# LoRaPi-0.net
KiCad netlist of a schematic drawn in EAGLE
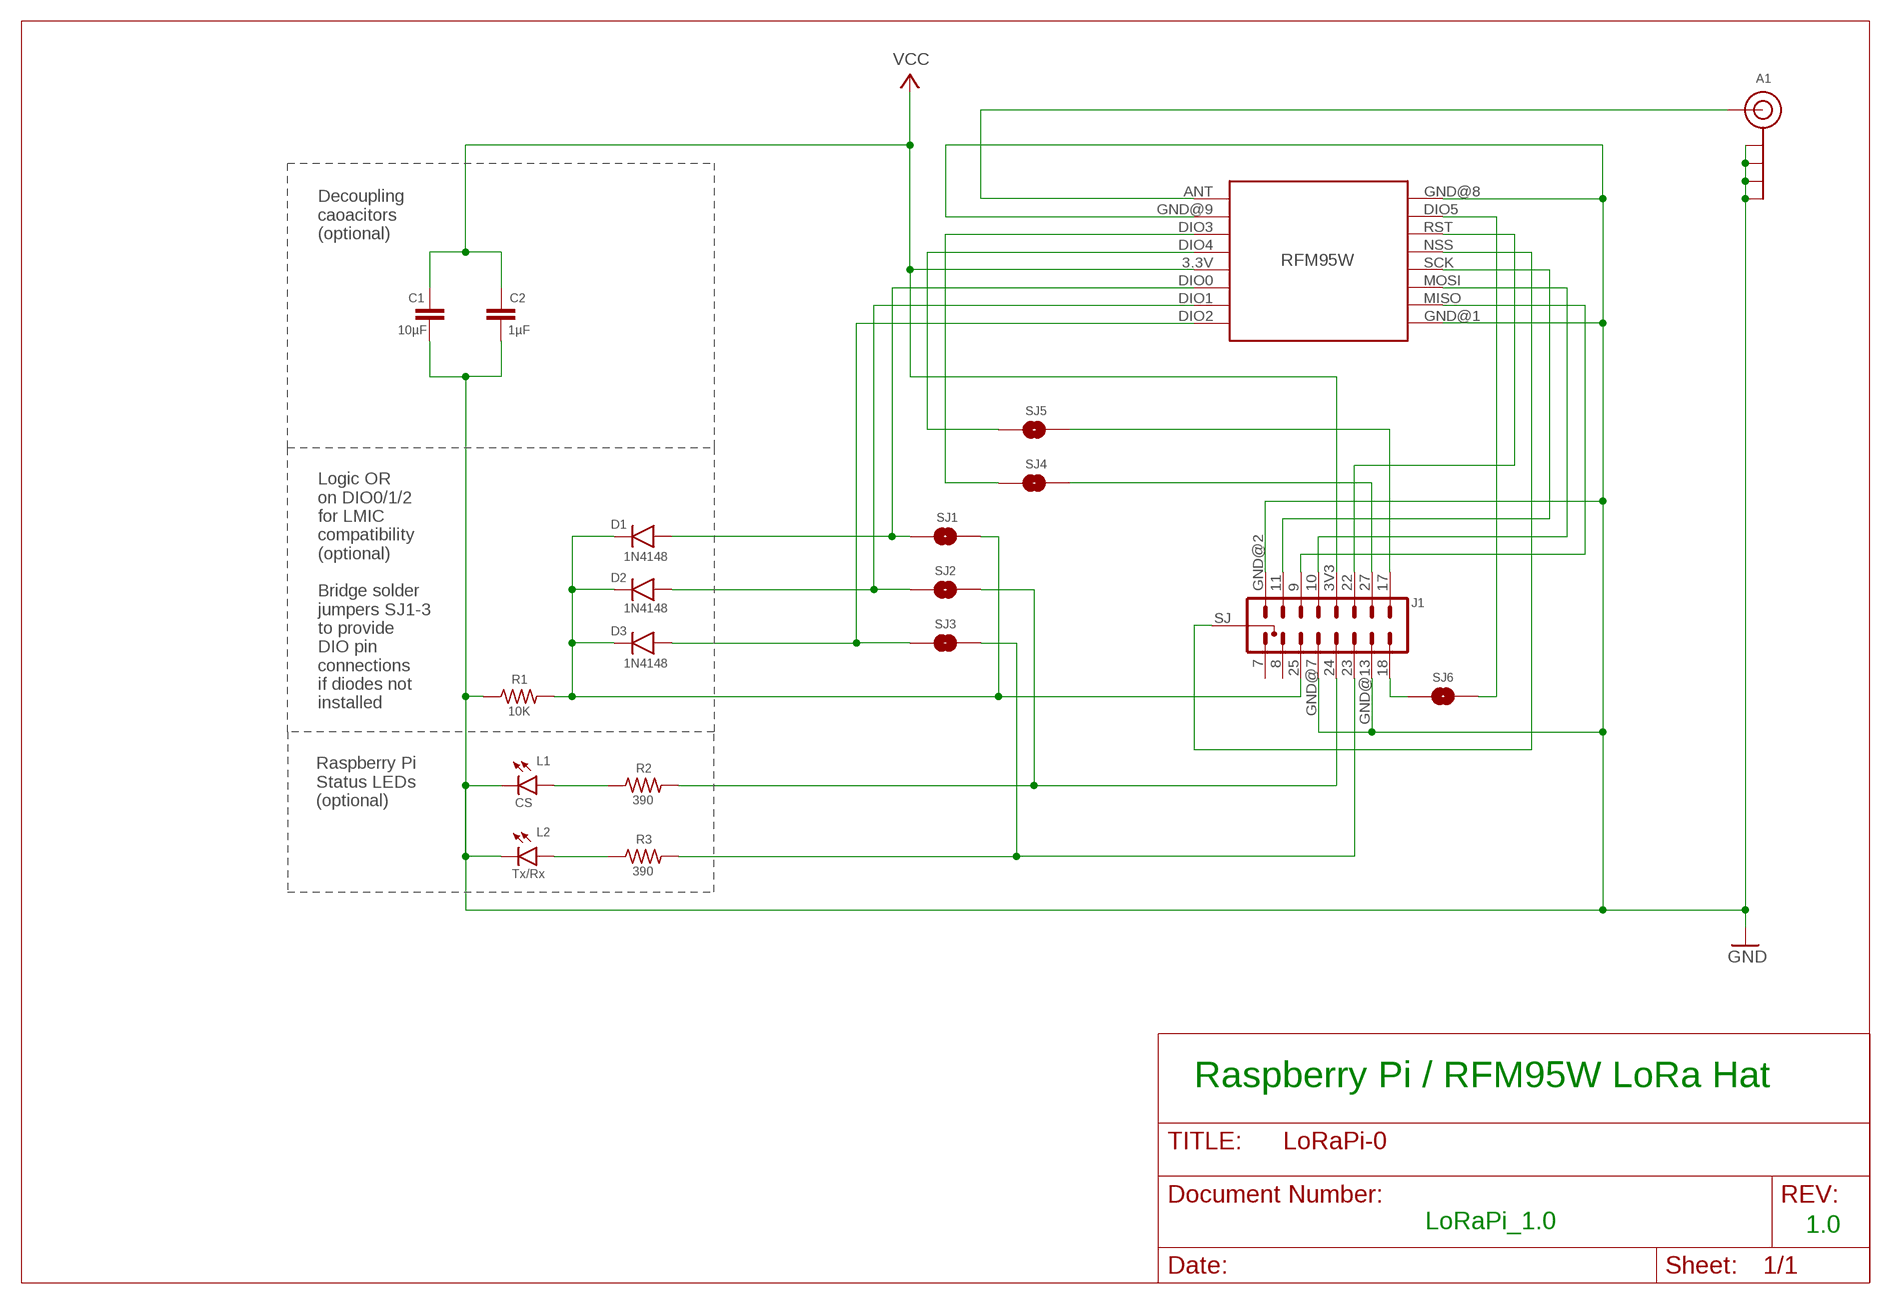
[diagram p0: schematic, sheet 1]

(export (version "E")
  (design (tool "Eeschema 10.0.6"))
  (components
    (comp (ref "A1")
      (value "U.FL-SMA-EDGE-COMBO")
      (footprint "eagle-import:U.FL-SMA-EDGE-COMBO")
      (libsource (lib "eagle-import") (part "U.FL-SMA-EDGE-COMBO"))
    )
    (comp (ref "C1")
      (value "10µF")
      (footprint "eagle-import:C0805")
      (libsource (lib "eagle-import") (part "CAPACITOR"))
    )
    (comp (ref "C2")
      (value "1µF")
      (footprint "eagle-import:C0805")
      (libsource (lib "eagle-import") (part "CAPACITOR"))
    )
    (comp (ref "D1")
      (value "1N4148")
      (footprint "eagle-import:SOD-123")
      (libsource (lib "eagle-import") (part "1N4148SMD"))
    )
    (comp (ref "D2")
      (value "1N4148")
      (footprint "eagle-import:SOD-123")
      (libsource (lib "eagle-import") (part "1N4148SMD"))
    )
    (comp (ref "D3")
      (value "1N4148")
      (footprint "eagle-import:SOD-123")
      (libsource (lib "eagle-import") (part "1N4148SMD"))
    )
    (comp (ref "J1")
      (value "HEADER-2X8-RFM95W-PI")
      (footprint "eagle-import:CONN_2X8-RFM-PI")
      (libsource (lib "eagle-import") (part "HEADER-2X8-RFM95W-PI"))
    )
    (comp (ref "L1")
      (value "CS")
      (footprint "eagle-import:CHIP-LED0805")
      (libsource (lib "eagle-import") (part "LEDCHIP-LED0805"))
    )
    (comp (ref "L2")
      (value "Tx/Rx")
      (footprint "eagle-import:CHIP-LED0805")
      (libsource (lib "eagle-import") (part "LEDCHIP-LED0805"))
    )
    (comp (ref "R1")
      (value "10K")
      (footprint "eagle-import:R0805")
      (libsource (lib "eagle-import") (part "R-US_R0805"))
    )
    (comp (ref "R2")
      (value "390")
      (footprint "eagle-import:R0805")
      (libsource (lib "eagle-import") (part "R-US_R0805"))
    )
    (comp (ref "R3")
      (value "390")
      (footprint "eagle-import:R0805")
      (libsource (lib "eagle-import") (part "R-US_R0805"))
    )
    (comp (ref "RFM95W")
      (value "RFM95W-LORA")
      (footprint "eagle-import:RFM95W-LORA")
      (libsource (lib "eagle-import") (part "RFM95W-LORA"))
    )
    (comp (ref "SJ1") (value "SJ") (footprint "eagle-import:SJ") (libsource (lib "eagle-import") (part "SJ")))
    (comp (ref "SJ2") (value "SJ") (footprint "eagle-import:SJ") (libsource (lib "eagle-import") (part "SJ")))
    (comp (ref "SJ3") (value "SJ") (footprint "eagle-import:SJ") (libsource (lib "eagle-import") (part "SJ")))
    (comp (ref "SJ4") (value "SJ") (footprint "eagle-import:SJ") (libsource (lib "eagle-import") (part "SJ")))
    (comp (ref "SJ5") (value "SJ") (footprint "eagle-import:SJ") (libsource (lib "eagle-import") (part "SJ")))
    (comp (ref "SJ6") (value "SJ") (footprint "eagle-import:SJ") (libsource (lib "eagle-import") (part "SJ")))
  )
  (nets
    (net (code "1") (name "GND") (class "Default")
      (node (ref "A1") (pin "GND@1A") (pinfunction "GND_GND@1A") (pintype "bidirectional"))
      (node (ref "A1") (pin "GND@1B") (pinfunction "GND_GND@1B") (pintype "bidirectional"))
      (node (ref "A1") (pin "GND@2A") (pinfunction "GND_GND@2A") (pintype "bidirectional"))
      (node (ref "A1") (pin "GND@2B") (pinfunction "GND_GND@2B") (pintype "bidirectional"))
      (node (ref "C1") (pin "2") (pinfunction "2_2") (pintype "passive"))
      (node (ref "C2") (pin "2") (pinfunction "2_2") (pintype "passive"))
      (node (ref "J1") (pin "GND@13") (pinfunction "15_GND@13") (pintype "passive"))
      (node (ref "J1") (pin "GND@2") (pinfunction "8_GND@2") (pintype "passive"))
      (node (ref "J1") (pin "GND@7") (pinfunction "12_GND@7") (pintype "passive"))
      (node (ref "L1") (pin "C") (pinfunction "C_C") (pintype "passive"))
      (node (ref "L2") (pin "C") (pinfunction "C_C") (pintype "passive"))
      (node (ref "R1") (pin "1") (pinfunction "1_1") (pintype "passive"))
      (node (ref "RFM95W") (pin "GND@1") (pinfunction "GND.1_GND@1") (pintype "power_in"))
      (node (ref "RFM95W") (pin "GND@8") (pinfunction "GND.2_GND@8") (pintype "power_in"))
      (node (ref "RFM95W") (pin "GND@9") (pinfunction "GND.3_GND@9") (pintype "power_in"))
    )
    (net (code "2") (name "Net-(A1-PadSIG)") (class "Default")
      (node (ref "A1") (pin "SIG") (pinfunction "SIG_SIG") (pintype "bidirectional"))
      (node (ref "RFM95W") (pin "ANT") (pinfunction "ANT_ANT") (pintype "passive"))
    )
    (net (code "3") (name "Net-(D1-Pad2)") (class "Default")
      (node (ref "D1") (pin "2") (pinfunction "2_2") (pintype "bidirectional"))
      (node (ref "RFM95W") (pin "DIO0") (pinfunction "DIO0_DIO0") (pintype "bidirectional"))
      (node (ref "SJ1") (pin "1") (pinfunction "1_1") (pintype "passive"))
    )
    (net (code "4") (name "Net-(D2-Pad2)") (class "Default")
      (node (ref "D2") (pin "2") (pinfunction "2_2") (pintype "bidirectional"))
      (node (ref "RFM95W") (pin "DIO1") (pinfunction "DIO1_DIO1") (pintype "bidirectional"))
      (node (ref "SJ2") (pin "1") (pinfunction "1_1") (pintype "passive"))
    )
    (net (code "5") (name "Net-(D3-Pad2)") (class "Default")
      (node (ref "D3") (pin "2") (pinfunction "2_2") (pintype "bidirectional"))
      (node (ref "RFM95W") (pin "DIO2") (pinfunction "DIO2_DIO2") (pintype "bidirectional"))
      (node (ref "SJ3") (pin "1") (pinfunction "1_1") (pintype "passive"))
    )
    (net (code "6") (name "Net-(J1-1)") (class "Default")
      (node (ref "J1") (pin "17") (pinfunction "1_17") (pintype "passive"))
      (node (ref "SJ5") (pin "2") (pinfunction "2_2") (pintype "passive"))
    )
    (net (code "7") (name "Net-(J1-2)") (class "Default")
      (node (ref "J1") (pin "27") (pinfunction "2_27") (pintype "passive"))
      (node (ref "SJ4") (pin "2") (pinfunction "2_2") (pintype "passive"))
    )
    (net (code "8") (name "Net-(J1-3)") (class "Default")
      (node (ref "J1") (pin "22") (pinfunction "3_22") (pintype "passive"))
      (node (ref "RFM95W") (pin "RST") (pinfunction "RST_RST") (pintype "bidirectional"))
    )
    (net (code "9") (name "Net-(J1-5)") (class "Default")
      (node (ref "J1") (pin "10") (pinfunction "5_10") (pintype "passive"))
      (node (ref "RFM95W") (pin "MOSI") (pinfunction "MOSI_MOSI") (pintype "bidirectional"))
    )
    (net (code "10") (name "Net-(J1-6)") (class "Default")
      (node (ref "J1") (pin "9") (pinfunction "6_9") (pintype "passive"))
      (node (ref "RFM95W") (pin "MISO") (pinfunction "MISO_MISO") (pintype "bidirectional"))
    )
    (net (code "11") (name "Net-(J1-7)") (class "Default")
      (node (ref "J1") (pin "11") (pinfunction "7_11") (pintype "passive"))
      (node (ref "RFM95W") (pin "SCK") (pinfunction "SCK_SCK") (pintype "bidirectional"))
    )
    (net (code "12") (name "Net-(J1-8-9)") (class "Default")
      (node (ref "J1") (pin "SJ") (pinfunction "8-9_SJ") (pintype "passive"))
      (node (ref "RFM95W") (pin "NSS") (pinfunction "NSS_NSS") (pintype "bidirectional"))
    )
    (net (code "13") (name "Net-(J1-11)") (class "Default")
      (node (ref "D1") (pin "1") (pinfunction "1_1") (pintype "bidirectional"))
      (node (ref "D2") (pin "1") (pinfunction "1_1") (pintype "bidirectional"))
      (node (ref "D3") (pin "1") (pinfunction "1_1") (pintype "bidirectional"))
      (node (ref "J1") (pin "25") (pinfunction "11_25") (pintype "passive"))
      (node (ref "R1") (pin "2") (pinfunction "2_2") (pintype "passive"))
      (node (ref "SJ1") (pin "2") (pinfunction "2_2") (pintype "passive"))
    )
    (net (code "14") (name "Net-(J1-13)") (class "Default")
      (node (ref "J1") (pin "24") (pinfunction "13_24") (pintype "passive"))
      (node (ref "R2") (pin "2") (pinfunction "2_2") (pintype "passive"))
      (node (ref "SJ2") (pin "2") (pinfunction "2_2") (pintype "passive"))
    )
    (net (code "15") (name "Net-(J1-14)") (class "Default")
      (node (ref "J1") (pin "23") (pinfunction "14_23") (pintype "passive"))
      (node (ref "R3") (pin "2") (pinfunction "2_2") (pintype "passive"))
      (node (ref "SJ3") (pin "2") (pinfunction "2_2") (pintype "passive"))
    )
    (net (code "16") (name "Net-(J1-16)") (class "Default")
      (node (ref "J1") (pin "18") (pinfunction "16_18") (pintype "passive"))
      (node (ref "SJ6") (pin "1") (pinfunction "1_1") (pintype "passive"))
    )
    (net (code "17") (name "Net-(L1-PadA)") (class "Default")
      (node (ref "L1") (pin "A") (pinfunction "A_A") (pintype "passive"))
      (node (ref "R2") (pin "1") (pinfunction "1_1") (pintype "passive"))
    )
    (net (code "18") (name "Net-(L2-PadA)") (class "Default")
      (node (ref "L2") (pin "A") (pinfunction "A_A") (pintype "passive"))
      (node (ref "R3") (pin "1") (pinfunction "1_1") (pintype "passive"))
    )
    (net (code "19") (name "Net-(RFM95W-PadDIO3)") (class "Default")
      (node (ref "RFM95W") (pin "DIO3") (pinfunction "DIO3_DIO3") (pintype "bidirectional"))
      (node (ref "SJ4") (pin "1") (pinfunction "1_1") (pintype "passive"))
    )
    (net (code "20") (name "Net-(RFM95W-PadDIO4)") (class "Default")
      (node (ref "RFM95W") (pin "DIO4") (pinfunction "DIO4_DIO4") (pintype "bidirectional"))
      (node (ref "SJ5") (pin "1") (pinfunction "1_1") (pintype "passive"))
    )
    (net (code "21") (name "Net-(RFM95W-PadDIO5)") (class "Default")
      (node (ref "RFM95W") (pin "DIO5") (pinfunction "DIO5_DIO5") (pintype "bidirectional"))
      (node (ref "SJ6") (pin "2") (pinfunction "2_2") (pintype "passive"))
    )
    (net (code "22") (name "VCC") (class "Default")
      (node (ref "C1") (pin "1") (pinfunction "1_1") (pintype "passive"))
      (node (ref "C2") (pin "1") (pinfunction "1_1") (pintype "passive"))
      (node (ref "J1") (pin "3V3") (pinfunction "4_3V3") (pintype "passive"))
      (node (ref "RFM95W") (pin "3.3V") (pinfunction "3.3V_3.3V") (pintype "power_in"))
    )
    (net (code "23") (name "unconnected-(J1-9-Pad7)") (class "Default")
      (node (ref "J1") (pin "7") (pinfunction "9_7") (pintype "passive"))
    )
    (net (code "24") (name "unconnected-(J1-10-Pad8)") (class "Default")
      (node (ref "J1") (pin "8") (pinfunction "10_8") (pintype "passive"))
    )
  )
)
